# v1_0.net
KiCad netlist of a schematic drawn in Altium Designer
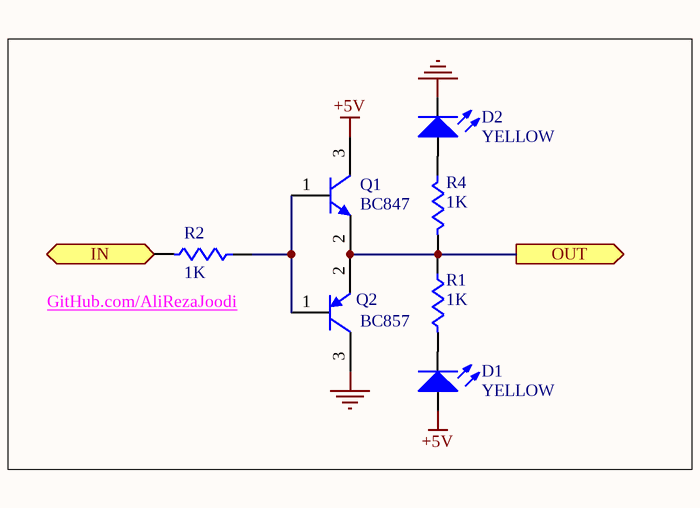
[diagram p0: v1.0.SchDoc]

(export (version "E")
  (design (tool "Eeschema 10.0.6"))
  (components
    (comp (ref "D1")
      (value "YELLOW")
      (footprint "0805_Diode")
      (description "Typical INFRARED GaAs LED")
      (fields (field (name "MANUFACTURER") "Generic Components") (field (name "PUBLISHER") "Altium Limited"))
      (libsource (lib "my Libraries") (part "Optical Transmitter"))
    )
    (comp (ref "D2")
      (value "YELLOW")
      (footprint "0805_Diode")
      (description "Typical INFRARED GaAs LED")
      (fields (field (name "MANUFACTURER") "Generic Components") (field (name "PUBLISHER") "Altium Limited"))
      (libsource (lib "my Libraries") (part "Optical Transmitter"))
    )
    (comp (ref "Q1")
      (value "BC847")
      (footprint "SOT23-3N")
      (description "Silicon Bipolar Transistor")
      (libsource (lib "my Libraries") (part "BC847"))
    )
    (comp (ref "Q2")
      (value "BC857")
      (footprint "SOT23-3N")
      (description "Silicon Bipolar Transistor")
      (libsource (lib "my Libraries") (part "BC857"))
    )
    (comp (ref "R1")
      (value "1K")
      (footprint "0805")
      (description "Resistor")
      (fields (field (name "MANUFACTURER") "Generic Components") (field (name "PUBLISHER") "Altium Limited"))
      (libsource (lib "Miscellaneous Devices") (part "Res1"))
    )
    (comp (ref "R2")
      (value "1K")
      (footprint "0805")
      (description "Resistor")
      (fields (field (name "MANUFACTURER") "Generic Components") (field (name "PUBLISHER") "Altium Limited"))
      (libsource (lib "Miscellaneous Devices") (part "Res1"))
    )
    (comp (ref "R4")
      (value "1K")
      (footprint "0805")
      (description "Resistor")
      (fields (field (name "MANUFACTURER") "Generic Components") (field (name "PUBLISHER") "Altium Limited"))
      (libsource (lib "Miscellaneous Devices") (part "Res1"))
    )
  )
  (nets
    (net (code "1") (name "+5V") (class "Default")
      (node (ref "D1") (pin "1") (pinfunction "A_1") (pintype "passive"))
      (node (ref "Q1") (pin "3") (pinfunction "C_3") (pintype "passive"))
    )
    (net (code "2") (name "/IN") (class "Default")
      (node (ref "R2") (pin "2") (pinfunction "2_2") (pintype "passive"))
    )
    (net (code "3") (name "/OUT") (class "Default")
      (node (ref "Q1") (pin "2") (pinfunction "E_2") (pintype "passive"))
      (node (ref "Q2") (pin "2") (pinfunction "E_2") (pintype "passive"))
      (node (ref "R1") (pin "1") (pinfunction "1_1") (pintype "passive"))
      (node (ref "R4") (pin "2") (pinfunction "2_2") (pintype "passive"))
    )
    (net (code "4") (name "GND") (class "Default")
      (node (ref "D2") (pin "2") (pinfunction "K_2") (pintype "passive"))
      (node (ref "Q2") (pin "3") (pinfunction "C_3") (pintype "passive"))
    )
    (net (code "5") (name "Net-(D1-K)") (class "Default")
      (node (ref "D1") (pin "2") (pinfunction "K_2") (pintype "passive"))
      (node (ref "R1") (pin "2") (pinfunction "2_2") (pintype "passive"))
    )
    (net (code "6") (name "Net-(D2-A)") (class "Default")
      (node (ref "D2") (pin "1") (pinfunction "A_1") (pintype "passive"))
      (node (ref "R4") (pin "1") (pinfunction "1_1") (pintype "passive"))
    )
    (net (code "7") (name "Net-(Q1-B)") (class "Default")
      (node (ref "Q1") (pin "1") (pinfunction "B_1") (pintype "passive"))
      (node (ref "Q2") (pin "1") (pinfunction "B_1") (pintype "passive"))
      (node (ref "R2") (pin "1") (pinfunction "1_1") (pintype "passive"))
    )
  )
)
